# ExtBoard_20Pin.net
KiCad netlist of a schematic drawn in Altium Designer
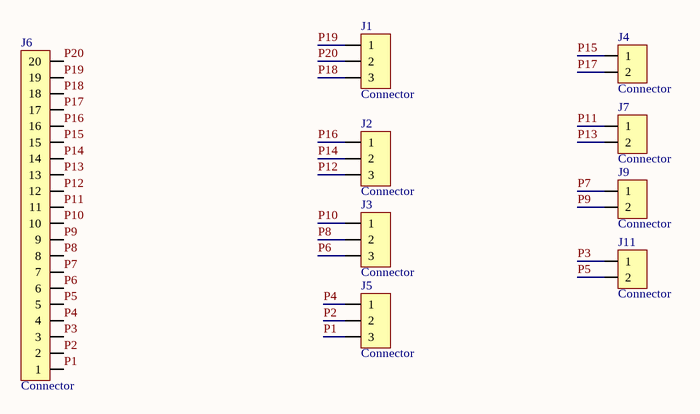
[diagram p0: ExtBoard 20Pin.SchDoc]

(export (version "E")
  (design (tool "Eeschema 10.0.6"))
  (components
    (comp (ref "J1")
      (value "Connector")
      (footprint "Connector:DG301 5mm 3p")
      (description "DG301 series")
      (libsource (lib "Connector") (part "DG301-5.0-3P12"))
    )
    (comp (ref "J2")
      (value "Connector")
      (footprint "Connector:DG301 5mm 3p")
      (description "DG301 series")
      (libsource (lib "Connector") (part "DG301-5.0-3P12"))
    )
    (comp (ref "J3")
      (value "Connector")
      (footprint "Connector:DG301 5mm 3p")
      (description "DG301 series")
      (libsource (lib "Connector") (part "DG301-5.0-3P12"))
    )
    (comp (ref "J4")
      (value "Connector")
      (footprint "Connector:DG301 5mm 2p")
      (description "DG301 series")
      (libsource (lib "Connector") (part "DG301-5.0-2P12"))
    )
    (comp (ref "J5")
      (value "Connector")
      (footprint "Connector:DG301 5mm 3p")
      (description "DG301 series")
      (libsource (lib "Connector") (part "DG301-5.0-3P12"))
    )
    (comp (ref "J6")
      (value "Connector")
      (footprint "Connector:LINE 2.54 x 20D (2 x 10)")
      (description "Vert, Dbl line, Male")
      (libsource (lib "Connector") (part "PLD-20 (2 x 10)"))
    )
    (comp (ref "J7")
      (value "Connector")
      (footprint "Connector:DG301 5mm 2p")
      (description "DG301 series")
      (libsource (lib "Connector") (part "DG301-5.0-2P12"))
    )
    (comp (ref "J9")
      (value "Connector")
      (footprint "Connector:DG301 5mm 2p")
      (description "DG301 series")
      (libsource (lib "Connector") (part "DG301-5.0-2P12"))
    )
    (comp (ref "J11")
      (value "Connector")
      (footprint "Connector:DG301 5mm 2p")
      (description "DG301 series")
      (libsource (lib "Connector") (part "DG301-5.0-2P12"))
    )
  )
  (nets
    (net (code "1") (name "/P1") (class "Default")
      (node (ref "J5") (pin "3") (pinfunction "3_3") (pintype "passive"))
      (node (ref "J6") (pin "1") (pinfunction "1_1") (pintype "passive"))
    )
    (net (code "2") (name "/P2") (class "Default")
      (node (ref "J5") (pin "2") (pinfunction "2_2") (pintype "passive"))
      (node (ref "J6") (pin "2") (pinfunction "2_2") (pintype "passive"))
    )
    (net (code "3") (name "/P3") (class "Default")
      (node (ref "J11") (pin "1") (pinfunction "1_1") (pintype "passive"))
      (node (ref "J6") (pin "3") (pinfunction "3_3") (pintype "passive"))
    )
    (net (code "4") (name "/P4") (class "Default")
      (node (ref "J5") (pin "1") (pinfunction "1_1") (pintype "passive"))
      (node (ref "J6") (pin "4") (pinfunction "4_4") (pintype "passive"))
    )
    (net (code "5") (name "/P5") (class "Default")
      (node (ref "J11") (pin "2") (pinfunction "2_2") (pintype "passive"))
      (node (ref "J6") (pin "5") (pinfunction "5_5") (pintype "passive"))
    )
    (net (code "6") (name "/P6") (class "Default")
      (node (ref "J3") (pin "3") (pinfunction "3_3") (pintype "passive"))
      (node (ref "J6") (pin "6") (pinfunction "6_6") (pintype "passive"))
    )
    (net (code "7") (name "/P7") (class "Default")
      (node (ref "J6") (pin "7") (pinfunction "7_7") (pintype "passive"))
      (node (ref "J9") (pin "1") (pinfunction "1_1") (pintype "passive"))
    )
    (net (code "8") (name "/P8") (class "Default")
      (node (ref "J3") (pin "2") (pinfunction "2_2") (pintype "passive"))
      (node (ref "J6") (pin "8") (pinfunction "8_8") (pintype "passive"))
    )
    (net (code "9") (name "/P9") (class "Default")
      (node (ref "J6") (pin "9") (pinfunction "9_9") (pintype "passive"))
      (node (ref "J9") (pin "2") (pinfunction "2_2") (pintype "passive"))
    )
    (net (code "10") (name "/P10") (class "Default")
      (node (ref "J3") (pin "1") (pinfunction "1_1") (pintype "passive"))
      (node (ref "J6") (pin "10") (pinfunction "10_10") (pintype "passive"))
    )
    (net (code "11") (name "/P11") (class "Default")
      (node (ref "J6") (pin "11") (pinfunction "11_11") (pintype "passive"))
      (node (ref "J7") (pin "1") (pinfunction "1_1") (pintype "passive"))
    )
    (net (code "12") (name "/P12") (class "Default")
      (node (ref "J2") (pin "3") (pinfunction "3_3") (pintype "passive"))
      (node (ref "J6") (pin "12") (pinfunction "12_12") (pintype "passive"))
    )
    (net (code "13") (name "/P13") (class "Default")
      (node (ref "J6") (pin "13") (pinfunction "13_13") (pintype "passive"))
      (node (ref "J7") (pin "2") (pinfunction "2_2") (pintype "passive"))
    )
    (net (code "14") (name "/P14") (class "Default")
      (node (ref "J2") (pin "2") (pinfunction "2_2") (pintype "passive"))
      (node (ref "J6") (pin "14") (pinfunction "14_14") (pintype "passive"))
    )
    (net (code "15") (name "/P15") (class "Default")
      (node (ref "J4") (pin "1") (pinfunction "1_1") (pintype "passive"))
      (node (ref "J6") (pin "15") (pinfunction "15_15") (pintype "passive"))
    )
    (net (code "16") (name "/P16") (class "Default")
      (node (ref "J2") (pin "1") (pinfunction "1_1") (pintype "passive"))
      (node (ref "J6") (pin "16") (pinfunction "16_16") (pintype "passive"))
    )
    (net (code "17") (name "/P17") (class "Default")
      (node (ref "J4") (pin "2") (pinfunction "2_2") (pintype "passive"))
      (node (ref "J6") (pin "17") (pinfunction "17_17") (pintype "passive"))
    )
    (net (code "18") (name "/P18") (class "Default")
      (node (ref "J1") (pin "3") (pinfunction "3_3") (pintype "passive"))
      (node (ref "J6") (pin "18") (pinfunction "18_18") (pintype "passive"))
    )
    (net (code "19") (name "/P19") (class "Default")
      (node (ref "J1") (pin "1") (pinfunction "1_1") (pintype "passive"))
      (node (ref "J6") (pin "19") (pinfunction "19_19") (pintype "passive"))
    )
    (net (code "20") (name "/P20") (class "Default")
      (node (ref "J1") (pin "2") (pinfunction "2_2") (pintype "passive"))
      (node (ref "J6") (pin "20") (pinfunction "20_20") (pintype "passive"))
    )
  )
)
